# 10_-I2C-Switch.net
KiCad netlist of a schematic drawn in Altium Designer
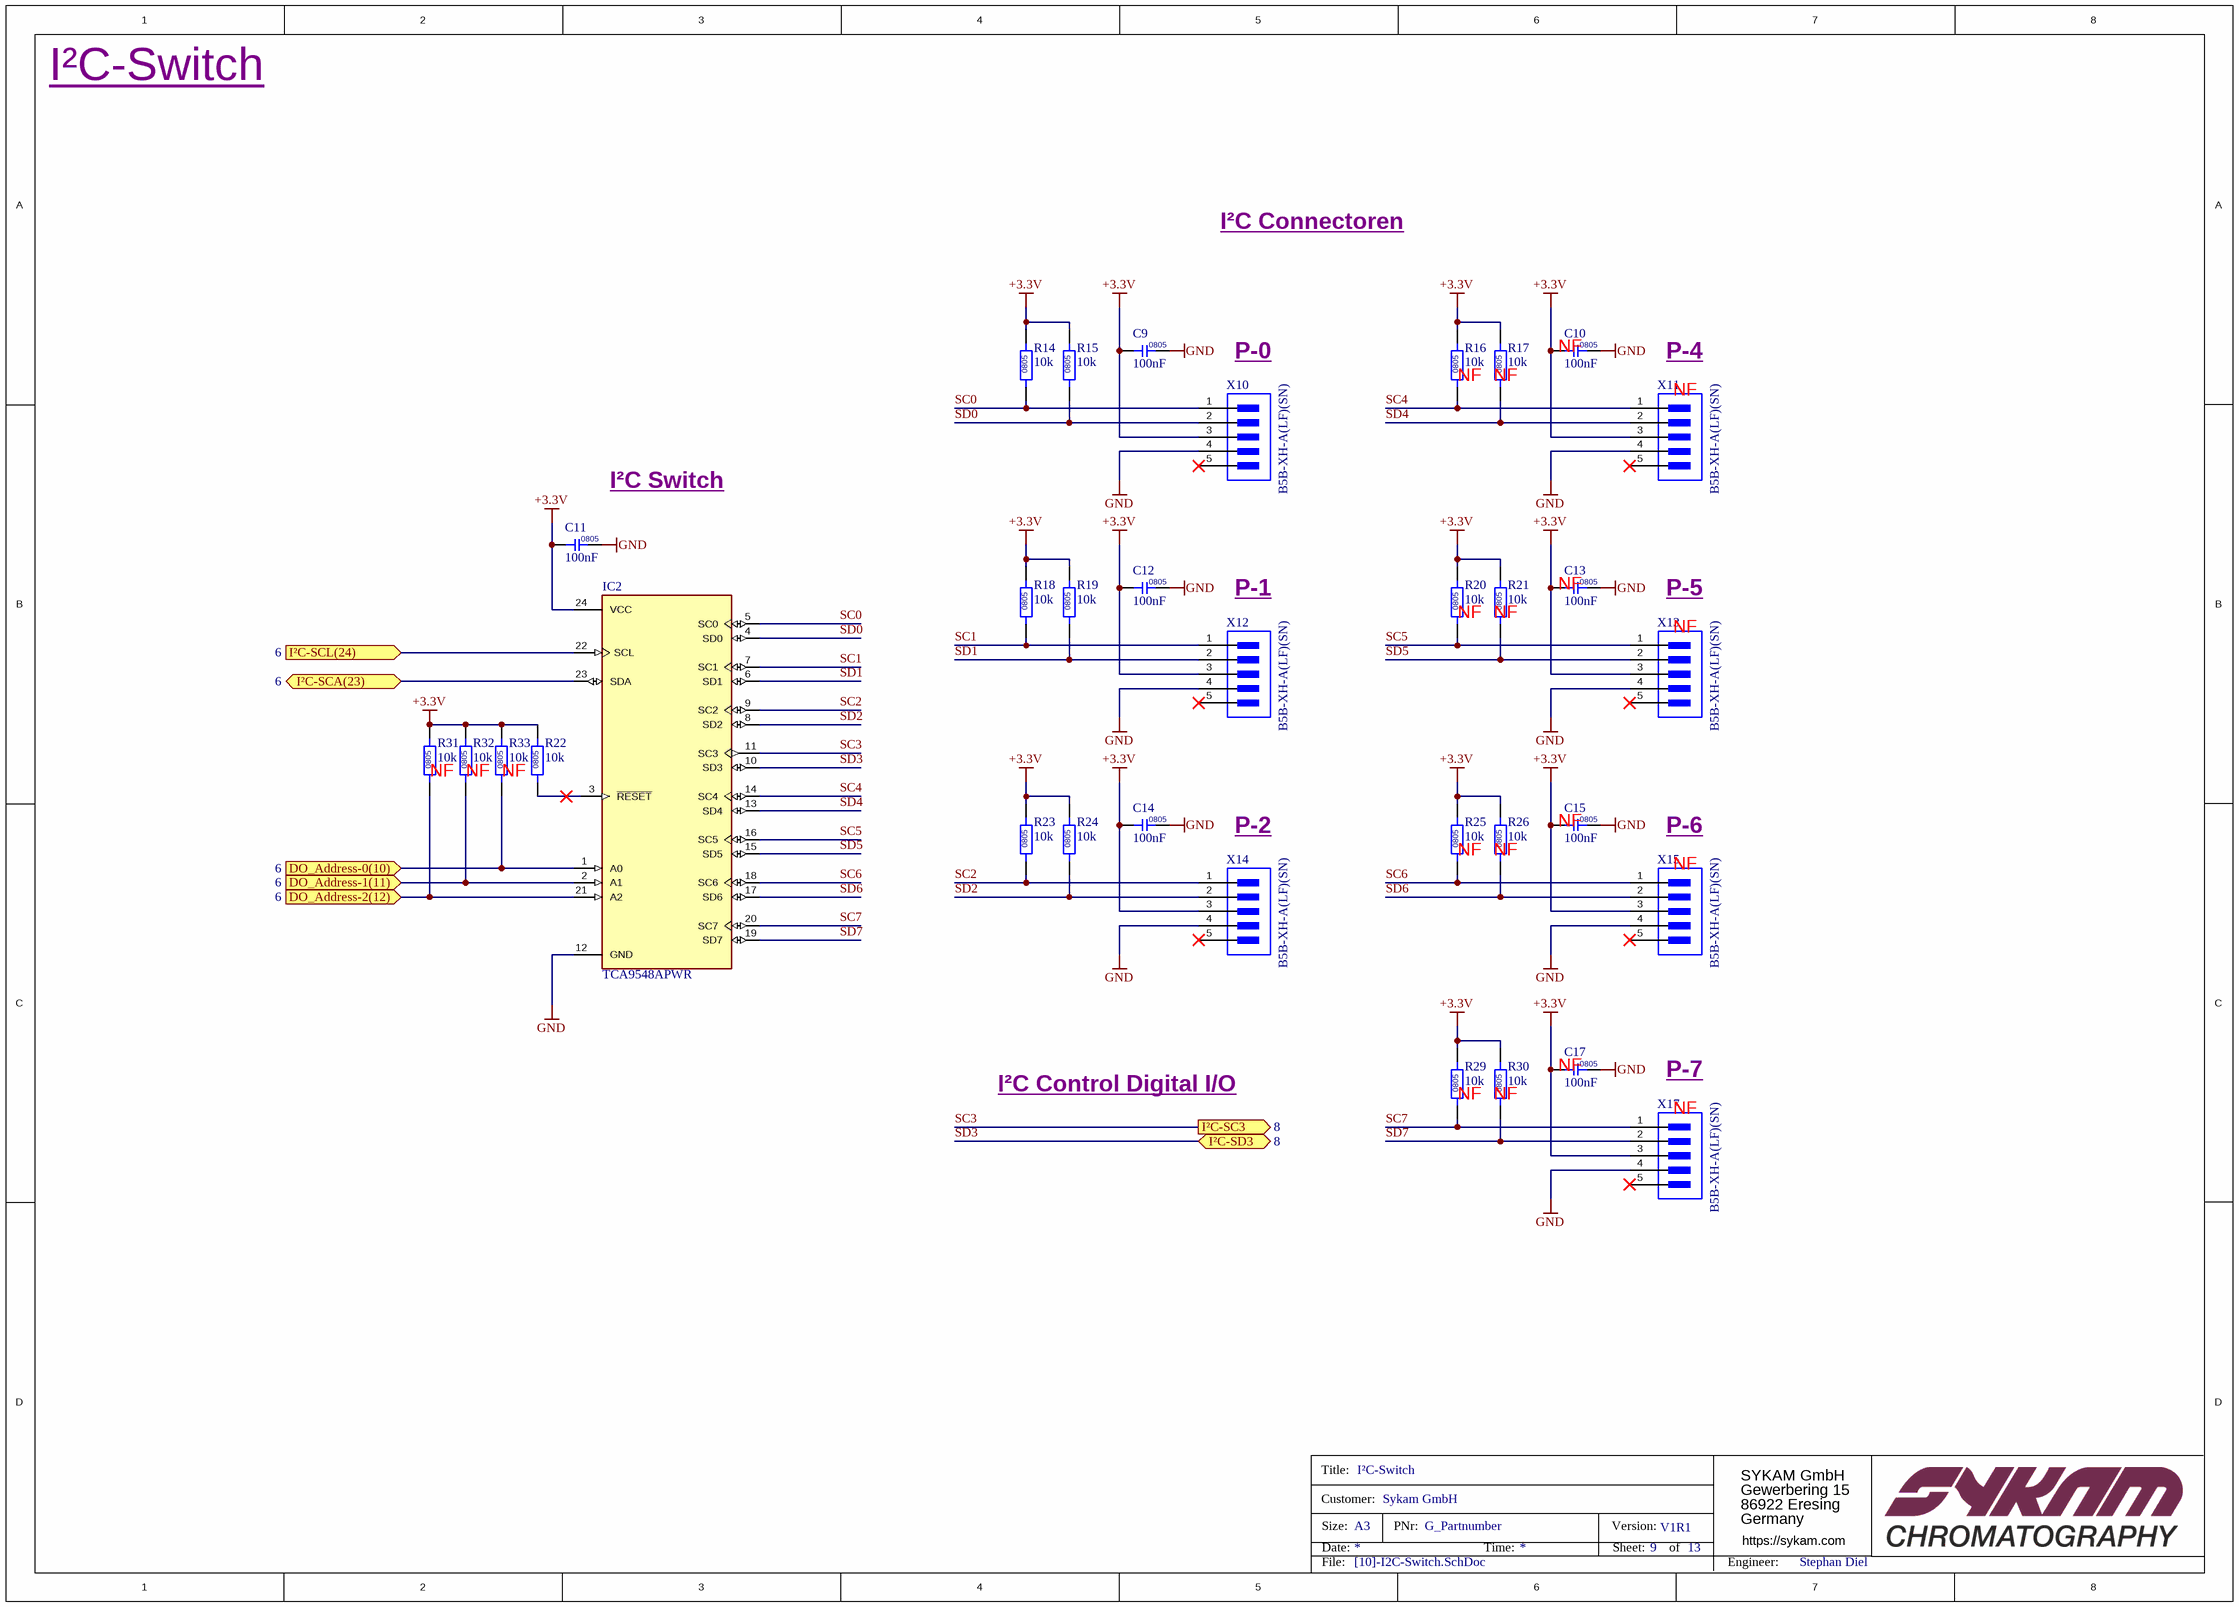
[diagram p0: [10]-I2C-Switch.SchDoc]

(export (version "E")
  (design (tool "Eeschema 10.0.6"))
  (components
    (comp (ref "C9")
      (value "100nF")
      (footprint "C0805")
      (description "CAP CER 0.1UF 50V X7R 0805")
      (fields
        (field (name "MANUFACTURER PART NUMBER") "CC0805KRX7R9BB104")
        (field (name "TOLERANCE") "10%")
        (field (name "PCBCHECKED") "initials after Checked")
        (field (name "SCHCHECKED") "Initials after checked")
      )
      (libsource (lib "ToradexMainBoard-V0I1") (part "C_100nF_CC0805KRX7R9BB104"))
    )
    (comp (ref "C10")
      (value "100nF")
      (footprint "C0805")
      (description "CAP CER 0.1UF 50V X7R 0805")
      (fields
        (field (name "MANUFACTURER PART NUMBER") "CC0805KRX7R9BB104")
        (field (name "TOLERANCE") "10%")
        (field (name "PCBCHECKED") "initials after Checked")
        (field (name "SCHCHECKED") "Initials after checked")
      )
      (libsource (lib "ToradexMainBoard-V0I1") (part "C_100nF_CC0805KRX7R9BB104"))
    )
    (comp (ref "C11")
      (value "100nF")
      (footprint "C0805")
      (description "CAP CER 0.1UF 50V X7R 0805")
      (fields
        (field (name "MANUFACTURER PART NUMBER") "CC0805KRX7R9BB104")
        (field (name "TOLERANCE") "10%")
        (field (name "PCBCHECKED") "initials after Checked")
        (field (name "SCHCHECKED") "Initials after checked")
      )
      (libsource (lib "ToradexMainBoard-V0I1") (part "C_100nF_CC0805KRX7R9BB104"))
    )
    (comp (ref "C12")
      (value "100nF")
      (footprint "C0805")
      (description "CAP CER 0.1UF 50V X7R 0805")
      (fields
        (field (name "MANUFACTURER PART NUMBER") "CC0805KRX7R9BB104")
        (field (name "TOLERANCE") "10%")
        (field (name "PCBCHECKED") "initials after Checked")
        (field (name "SCHCHECKED") "Initials after checked")
      )
      (libsource (lib "ToradexMainBoard-V0I1") (part "C_100nF_CC0805KRX7R9BB104"))
    )
    (comp (ref "C13")
      (value "100nF")
      (footprint "C0805")
      (description "CAP CER 0.1UF 50V X7R 0805")
      (fields
        (field (name "MANUFACTURER PART NUMBER") "CC0805KRX7R9BB104")
        (field (name "TOLERANCE") "10%")
        (field (name "PCBCHECKED") "initials after Checked")
        (field (name "SCHCHECKED") "Initials after checked")
      )
      (libsource (lib "ToradexMainBoard-V0I1") (part "C_100nF_CC0805KRX7R9BB104"))
    )
    (comp (ref "C14")
      (value "100nF")
      (footprint "C0805")
      (description "CAP CER 0.1UF 50V X7R 0805")
      (fields
        (field (name "MANUFACTURER PART NUMBER") "CC0805KRX7R9BB104")
        (field (name "TOLERANCE") "10%")
        (field (name "PCBCHECKED") "initials after Checked")
        (field (name "SCHCHECKED") "Initials after checked")
      )
      (libsource (lib "ToradexMainBoard-V0I1") (part "C_100nF_CC0805KRX7R9BB104"))
    )
    (comp (ref "C15")
      (value "100nF")
      (footprint "C0805")
      (description "CAP CER 0.1UF 50V X7R 0805")
      (fields
        (field (name "MANUFACTURER PART NUMBER") "CC0805KRX7R9BB104")
        (field (name "TOLERANCE") "10%")
        (field (name "PCBCHECKED") "initials after Checked")
        (field (name "SCHCHECKED") "Initials after checked")
      )
      (libsource (lib "ToradexMainBoard-V0I1") (part "C_100nF_CC0805KRX7R9BB104"))
    )
    (comp (ref "C17")
      (value "100nF")
      (footprint "C0805")
      (description "CAP CER 0.1UF 50V X7R 0805")
      (fields
        (field (name "MANUFACTURER PART NUMBER") "CC0805KRX7R9BB104")
        (field (name "TOLERANCE") "10%")
        (field (name "PCBCHECKED") "initials after Checked")
        (field (name "SCHCHECKED") "Initials after checked")
      )
      (libsource (lib "ToradexMainBoard-V0I1") (part "C_100nF_CC0805KRX7R9BB104"))
    )
    (comp (ref "IC2")
      (value "TCA9548APWR")
      (footprint "IC-TCA9548-TSSOP24")
      (description "IC I2C SW 8CH W/RESET 24TSSOP")
      (fields (field (name "MANUFACTURER") "Texas Instruments"))
      (libsource (lib "ToradexMainBoard-V0I1") (part "IC_TCA9548APWR"))
    )
    (comp (ref "R14")
      (value "10k")
      (footprint "R0805")
      (description "RES SMD 10K OHM 1% 1/8W 0805")
      (fields
        (field (name "MANUFACTURER PART NUMBER") "RC0805FR-0710KL")
        (field (name "TOLERANCE") "1%")
        (field (name "PCBCHECKED") "initials after Checked")
        (field (name "SCHCHECKED") "Initials after checked")
      )
      (libsource (lib "ToradexMainBoard-V0I1") (part "R_10k_RC0805FR-0710KL"))
    )
    (comp (ref "R15")
      (value "10k")
      (footprint "R0805")
      (description "RES SMD 10K OHM 1% 1/8W 0805")
      (fields
        (field (name "MANUFACTURER PART NUMBER") "RC0805FR-0710KL")
        (field (name "TOLERANCE") "1%")
        (field (name "PCBCHECKED") "initials after Checked")
        (field (name "SCHCHECKED") "Initials after checked")
      )
      (libsource (lib "ToradexMainBoard-V0I1") (part "R_10k_RC0805FR-0710KL"))
    )
    (comp (ref "R16")
      (value "10k")
      (footprint "R0805")
      (description "RES SMD 10K OHM 1% 1/8W 0805")
      (fields
        (field (name "MANUFACTURER PART NUMBER") "RC0805FR-0710KL")
        (field (name "TOLERANCE") "1%")
        (field (name "PCBCHECKED") "initials after Checked")
        (field (name "SCHCHECKED") "Initials after checked")
      )
      (libsource (lib "ToradexMainBoard-V0I1") (part "R_10k_RC0805FR-0710KL"))
    )
    (comp (ref "R17")
      (value "10k")
      (footprint "R0805")
      (description "RES SMD 10K OHM 1% 1/8W 0805")
      (fields
        (field (name "MANUFACTURER PART NUMBER") "RC0805FR-0710KL")
        (field (name "TOLERANCE") "1%")
        (field (name "PCBCHECKED") "initials after Checked")
        (field (name "SCHCHECKED") "Initials after checked")
      )
      (libsource (lib "ToradexMainBoard-V0I1") (part "R_10k_RC0805FR-0710KL"))
    )
    (comp (ref "R18")
      (value "10k")
      (footprint "R0805")
      (description "RES SMD 10K OHM 1% 1/8W 0805")
      (fields
        (field (name "MANUFACTURER PART NUMBER") "RC0805FR-0710KL")
        (field (name "TOLERANCE") "1%")
        (field (name "PCBCHECKED") "initials after Checked")
        (field (name "SCHCHECKED") "Initials after checked")
      )
      (libsource (lib "ToradexMainBoard-V0I1") (part "R_10k_RC0805FR-0710KL"))
    )
    (comp (ref "R19")
      (value "10k")
      (footprint "R0805")
      (description "RES SMD 10K OHM 1% 1/8W 0805")
      (fields
        (field (name "MANUFACTURER PART NUMBER") "RC0805FR-0710KL")
        (field (name "TOLERANCE") "1%")
        (field (name "PCBCHECKED") "initials after Checked")
        (field (name "SCHCHECKED") "Initials after checked")
      )
      (libsource (lib "ToradexMainBoard-V0I1") (part "R_10k_RC0805FR-0710KL"))
    )
    (comp (ref "R20")
      (value "10k")
      (footprint "R0805")
      (description "RES SMD 10K OHM 1% 1/8W 0805")
      (fields
        (field (name "MANUFACTURER PART NUMBER") "RC0805FR-0710KL")
        (field (name "TOLERANCE") "1%")
        (field (name "PCBCHECKED") "initials after Checked")
        (field (name "SCHCHECKED") "Initials after checked")
      )
      (libsource (lib "ToradexMainBoard-V0I1") (part "R_10k_RC0805FR-0710KL"))
    )
    (comp (ref "R21")
      (value "10k")
      (footprint "R0805")
      (description "RES SMD 10K OHM 1% 1/8W 0805")
      (fields
        (field (name "MANUFACTURER PART NUMBER") "RC0805FR-0710KL")
        (field (name "TOLERANCE") "1%")
        (field (name "PCBCHECKED") "initials after Checked")
        (field (name "SCHCHECKED") "Initials after checked")
      )
      (libsource (lib "ToradexMainBoard-V0I1") (part "R_10k_RC0805FR-0710KL"))
    )
    (comp (ref "R22")
      (value "10k")
      (footprint "R0805")
      (description "RES SMD 10K OHM 1% 1/8W 0805")
      (fields
        (field (name "MANUFACTURER PART NUMBER") "RC0805FR-0710KL")
        (field (name "TOLERANCE") "1%")
        (field (name "PCBCHECKED") "initials after Checked")
        (field (name "SCHCHECKED") "Initials after checked")
      )
      (libsource (lib "ToradexMainBoard-V0I1") (part "R_10k_RC0805FR-0710KL"))
    )
    (comp (ref "R23")
      (value "10k")
      (footprint "R0805")
      (description "RES SMD 10K OHM 1% 1/8W 0805")
      (fields
        (field (name "MANUFACTURER PART NUMBER") "RC0805FR-0710KL")
        (field (name "TOLERANCE") "1%")
        (field (name "PCBCHECKED") "initials after Checked")
        (field (name "SCHCHECKED") "Initials after checked")
      )
      (libsource (lib "ToradexMainBoard-V0I1") (part "R_10k_RC0805FR-0710KL"))
    )
    (comp (ref "R24")
      (value "10k")
      (footprint "R0805")
      (description "RES SMD 10K OHM 1% 1/8W 0805")
      (fields
        (field (name "MANUFACTURER PART NUMBER") "RC0805FR-0710KL")
        (field (name "TOLERANCE") "1%")
        (field (name "PCBCHECKED") "initials after Checked")
        (field (name "SCHCHECKED") "Initials after checked")
      )
      (libsource (lib "ToradexMainBoard-V0I1") (part "R_10k_RC0805FR-0710KL"))
    )
    (comp (ref "R25")
      (value "10k")
      (footprint "R0805")
      (description "RES SMD 10K OHM 1% 1/8W 0805")
      (fields
        (field (name "MANUFACTURER PART NUMBER") "RC0805FR-0710KL")
        (field (name "TOLERANCE") "1%")
        (field (name "PCBCHECKED") "initials after Checked")
        (field (name "SCHCHECKED") "Initials after checked")
      )
      (libsource (lib "ToradexMainBoard-V0I1") (part "R_10k_RC0805FR-0710KL"))
    )
    (comp (ref "R26")
      (value "10k")
      (footprint "R0805")
      (description "RES SMD 10K OHM 1% 1/8W 0805")
      (fields
        (field (name "MANUFACTURER PART NUMBER") "RC0805FR-0710KL")
        (field (name "TOLERANCE") "1%")
        (field (name "PCBCHECKED") "initials after Checked")
        (field (name "SCHCHECKED") "Initials after checked")
      )
      (libsource (lib "ToradexMainBoard-V0I1") (part "R_10k_RC0805FR-0710KL"))
    )
    (comp (ref "R29")
      (value "10k")
      (footprint "R0805")
      (description "RES SMD 10K OHM 1% 1/8W 0805")
      (fields
        (field (name "MANUFACTURER PART NUMBER") "RC0805FR-0710KL")
        (field (name "TOLERANCE") "1%")
        (field (name "PCBCHECKED") "initials after Checked")
        (field (name "SCHCHECKED") "Initials after checked")
      )
      (libsource (lib "ToradexMainBoard-V0I1") (part "R_10k_RC0805FR-0710KL"))
    )
    (comp (ref "R30")
      (value "10k")
      (footprint "R0805")
      (description "RES SMD 10K OHM 1% 1/8W 0805")
      (fields
        (field (name "MANUFACTURER PART NUMBER") "RC0805FR-0710KL")
        (field (name "TOLERANCE") "1%")
        (field (name "PCBCHECKED") "initials after Checked")
        (field (name "SCHCHECKED") "Initials after checked")
      )
      (libsource (lib "ToradexMainBoard-V0I1") (part "R_10k_RC0805FR-0710KL"))
    )
    (comp (ref "R31")
      (value "10k")
      (footprint "R0805")
      (description "RES SMD 10K OHM 1% 1/8W 0805")
      (fields
        (field (name "MANUFACTURER PART NUMBER") "RC0805FR-0710KL")
        (field (name "TOLERANCE") "1%")
        (field (name "PCBCHECKED") "initials after Checked")
        (field (name "SCHCHECKED") "Initials after checked")
      )
      (libsource (lib "ToradexMainBoard-V0I1") (part "R_10k_RC0805FR-0710KL"))
    )
    (comp (ref "R32")
      (value "10k")
      (footprint "R0805")
      (description "RES SMD 10K OHM 1% 1/8W 0805")
      (fields
        (field (name "MANUFACTURER PART NUMBER") "RC0805FR-0710KL")
        (field (name "TOLERANCE") "1%")
        (field (name "PCBCHECKED") "initials after Checked")
        (field (name "SCHCHECKED") "Initials after checked")
      )
      (libsource (lib "ToradexMainBoard-V0I1") (part "R_10k_RC0805FR-0710KL"))
    )
    (comp (ref "R33")
      (value "10k")
      (footprint "R0805")
      (description "RES SMD 10K OHM 1% 1/8W 0805")
      (fields
        (field (name "MANUFACTURER PART NUMBER") "RC0805FR-0710KL")
        (field (name "TOLERANCE") "1%")
        (field (name "PCBCHECKED") "initials after Checked")
        (field (name "SCHCHECKED") "Initials after checked")
      )
      (libsource (lib "ToradexMainBoard-V0I1") (part "R_10k_RC0805FR-0710KL"))
    )
    (comp (ref "X10")
      (value "B5B-XH-A(LF)(SN)")
      (footprint "CON_ B5B-XH-A (LF)(SN)")
      (description "Conn Shrouded Header HDR 5 POS 2.5mm Solder ST Thru-Hole Box")
      (fields (field (name "MANUFACTURER") "JST"))
      (libsource (lib "ToradexMainBoard-V0I1") (part "CON_5p_B5B-XH-A(LF)(SN)"))
    )
    (comp (ref "X11")
      (value "B5B-XH-A(LF)(SN)")
      (footprint "CON_ B5B-XH-A (LF)(SN)")
      (description "Conn Shrouded Header HDR 5 POS 2.5mm Solder ST Thru-Hole Box")
      (fields (field (name "MANUFACTURER") "JST"))
      (libsource (lib "ToradexMainBoard-V0I1") (part "CON_5p_B5B-XH-A(LF)(SN)"))
    )
    (comp (ref "X12")
      (value "B5B-XH-A(LF)(SN)")
      (footprint "CON_ B5B-XH-A (LF)(SN)")
      (description "Conn Shrouded Header HDR 5 POS 2.5mm Solder ST Thru-Hole Box")
      (fields (field (name "MANUFACTURER") "JST"))
      (libsource (lib "ToradexMainBoard-V0I1") (part "CON_5p_B5B-XH-A(LF)(SN)"))
    )
    (comp (ref "X13")
      (value "B5B-XH-A(LF)(SN)")
      (footprint "CON_ B5B-XH-A (LF)(SN)")
      (description "Conn Shrouded Header HDR 5 POS 2.5mm Solder ST Thru-Hole Box")
      (fields (field (name "MANUFACTURER") "JST"))
      (libsource (lib "ToradexMainBoard-V0I1") (part "CON_5p_B5B-XH-A(LF)(SN)"))
    )
    (comp (ref "X14")
      (value "B5B-XH-A(LF)(SN)")
      (footprint "CON_ B5B-XH-A (LF)(SN)")
      (description "Conn Shrouded Header HDR 5 POS 2.5mm Solder ST Thru-Hole Box")
      (fields (field (name "MANUFACTURER") "JST"))
      (libsource (lib "ToradexMainBoard-V0I1") (part "CON_5p_B5B-XH-A(LF)(SN)"))
    )
    (comp (ref "X15")
      (value "B5B-XH-A(LF)(SN)")
      (footprint "CON_ B5B-XH-A (LF)(SN)")
      (description "Conn Shrouded Header HDR 5 POS 2.5mm Solder ST Thru-Hole Box")
      (fields (field (name "MANUFACTURER") "JST"))
      (libsource (lib "ToradexMainBoard-V0I1") (part "CON_5p_B5B-XH-A(LF)(SN)"))
    )
    (comp (ref "X17")
      (value "B5B-XH-A(LF)(SN)")
      (footprint "CON_ B5B-XH-A (LF)(SN)")
      (description "Conn Shrouded Header HDR 5 POS 2.5mm Solder ST Thru-Hole Box")
      (fields (field (name "MANUFACTURER") "JST"))
      (libsource (lib "ToradexMainBoard-V0I1") (part "CON_5p_B5B-XH-A(LF)(SN)"))
    )
  )
  (nets
    (net (code "1") (name "+3.3V") (class "Default")
      (node (ref "C10") (pin "1") (pinfunction "1_1") (pintype "passive"))
      (node (ref "C11") (pin "1") (pinfunction "1_1") (pintype "passive"))
      (node (ref "C12") (pin "1") (pinfunction "1_1") (pintype "passive"))
      (node (ref "C13") (pin "1") (pinfunction "1_1") (pintype "passive"))
      (node (ref "C14") (pin "1") (pinfunction "1_1") (pintype "passive"))
      (node (ref "C15") (pin "1") (pinfunction "1_1") (pintype "passive"))
      (node (ref "C17") (pin "1") (pinfunction "1_1") (pintype "passive"))
      (node (ref "C9") (pin "1") (pinfunction "1_1") (pintype "passive"))
      (node (ref "IC2") (pin "24") (pinfunction "VCC_24") (pintype "power_in"))
      (node (ref "R14") (pin "2") (pinfunction "2_2") (pintype "passive"))
      (node (ref "R15") (pin "2") (pinfunction "2_2") (pintype "passive"))
      (node (ref "R16") (pin "2") (pinfunction "2_2") (pintype "passive"))
      (node (ref "R17") (pin "2") (pinfunction "2_2") (pintype "passive"))
      (node (ref "R18") (pin "2") (pinfunction "2_2") (pintype "passive"))
      (node (ref "R19") (pin "2") (pinfunction "2_2") (pintype "passive"))
      (node (ref "R20") (pin "2") (pinfunction "2_2") (pintype "passive"))
      (node (ref "R21") (pin "2") (pinfunction "2_2") (pintype "passive"))
      (node (ref "R22") (pin "2") (pinfunction "2_2") (pintype "passive"))
      (node (ref "R23") (pin "2") (pinfunction "2_2") (pintype "passive"))
      (node (ref "R24") (pin "2") (pinfunction "2_2") (pintype "passive"))
      (node (ref "R25") (pin "2") (pinfunction "2_2") (pintype "passive"))
      (node (ref "R26") (pin "2") (pinfunction "2_2") (pintype "passive"))
      (node (ref "R29") (pin "2") (pinfunction "2_2") (pintype "passive"))
      (node (ref "R30") (pin "2") (pinfunction "2_2") (pintype "passive"))
      (node (ref "R31") (pin "2") (pinfunction "2_2") (pintype "passive"))
      (node (ref "R32") (pin "2") (pinfunction "2_2") (pintype "passive"))
      (node (ref "R33") (pin "2") (pinfunction "2_2") (pintype "passive"))
      (node (ref "X10") (pin "3") (pintype "passive"))
      (node (ref "X11") (pin "3") (pintype "passive"))
      (node (ref "X12") (pin "3") (pintype "passive"))
      (node (ref "X13") (pin "3") (pintype "passive"))
      (node (ref "X14") (pin "3") (pintype "passive"))
      (node (ref "X15") (pin "3") (pintype "passive"))
      (node (ref "X17") (pin "3") (pintype "passive"))
    )
    (net (code "2") (name "/DO_Address-0(10)") (class "Default")
      (node (ref "IC2") (pin "1") (pinfunction "A0_1") (pintype "input"))
      (node (ref "R33") (pin "1") (pinfunction "1_1") (pintype "passive"))
    )
    (net (code "3") (name "/DO_Address-1(11)") (class "Default")
      (node (ref "IC2") (pin "2") (pinfunction "A1_2") (pintype "input"))
      (node (ref "R32") (pin "1") (pinfunction "1_1") (pintype "passive"))
    )
    (net (code "4") (name "/DO_Address-2(12)") (class "Default")
      (node (ref "IC2") (pin "21") (pinfunction "A2_21") (pintype "input"))
      (node (ref "R31") (pin "1") (pinfunction "1_1") (pintype "passive"))
    )
    (net (code "5") (name "/I²C-SCA(23)") (class "Default")
      (node (ref "IC2") (pin "23") (pinfunction "SDA_23") (pintype "bidirectional"))
    )
    (net (code "6") (name "/I²C-SCL(24)") (class "Default")
      (node (ref "IC2") (pin "22") (pinfunction "SCL_22") (pintype "input"))
    )
    (net (code "7") (name "/SC0") (class "Default")
      (node (ref "IC2") (pin "5") (pinfunction "SC0_5") (pintype "bidirectional"))
      (node (ref "R14") (pin "1") (pinfunction "1_1") (pintype "passive"))
      (node (ref "X10") (pin "1") (pintype "passive"))
    )
    (net (code "8") (name "/SC1") (class "Default")
      (node (ref "IC2") (pin "7") (pinfunction "SC1_7") (pintype "bidirectional"))
      (node (ref "R18") (pin "1") (pinfunction "1_1") (pintype "passive"))
      (node (ref "X12") (pin "1") (pintype "passive"))
    )
    (net (code "9") (name "/SC2") (class "Default")
      (node (ref "IC2") (pin "9") (pinfunction "SC2_9") (pintype "bidirectional"))
      (node (ref "R23") (pin "1") (pinfunction "1_1") (pintype "passive"))
      (node (ref "X14") (pin "1") (pintype "passive"))
    )
    (net (code "10") (name "/SC3") (class "Default")
      (node (ref "IC2") (pin "11") (pinfunction "SC3_11") (pintype "output"))
    )
    (net (code "11") (name "/SC4") (class "Default")
      (node (ref "IC2") (pin "14") (pinfunction "SC4_14") (pintype "bidirectional"))
      (node (ref "R16") (pin "1") (pinfunction "1_1") (pintype "passive"))
      (node (ref "X11") (pin "1") (pintype "passive"))
    )
    (net (code "12") (name "/SC5") (class "Default")
      (node (ref "IC2") (pin "16") (pinfunction "SC5_16") (pintype "bidirectional"))
      (node (ref "R20") (pin "1") (pinfunction "1_1") (pintype "passive"))
      (node (ref "X13") (pin "1") (pintype "passive"))
    )
    (net (code "13") (name "/SC6") (class "Default")
      (node (ref "IC2") (pin "18") (pinfunction "SC6_18") (pintype "bidirectional"))
      (node (ref "R25") (pin "1") (pinfunction "1_1") (pintype "passive"))
      (node (ref "X15") (pin "1") (pintype "passive"))
    )
    (net (code "14") (name "/SC7") (class "Default")
      (node (ref "IC2") (pin "20") (pinfunction "SC7_20") (pintype "bidirectional"))
      (node (ref "R29") (pin "1") (pinfunction "1_1") (pintype "passive"))
      (node (ref "X17") (pin "1") (pintype "passive"))
    )
    (net (code "15") (name "/SD0") (class "Default")
      (node (ref "IC2") (pin "4") (pinfunction "SD0_4") (pintype "bidirectional"))
      (node (ref "R15") (pin "1") (pinfunction "1_1") (pintype "passive"))
      (node (ref "X10") (pin "2") (pintype "passive"))
    )
    (net (code "16") (name "/SD1") (class "Default")
      (node (ref "IC2") (pin "6") (pinfunction "SD1_6") (pintype "bidirectional"))
      (node (ref "R19") (pin "1") (pinfunction "1_1") (pintype "passive"))
      (node (ref "X12") (pin "2") (pintype "passive"))
    )
    (net (code "17") (name "/SD2") (class "Default")
      (node (ref "IC2") (pin "8") (pinfunction "SD2_8") (pintype "bidirectional"))
      (node (ref "R24") (pin "1") (pinfunction "1_1") (pintype "passive"))
      (node (ref "X14") (pin "2") (pintype "passive"))
    )
    (net (code "18") (name "/SD3") (class "Default")
      (node (ref "IC2") (pin "10") (pinfunction "SD3_10") (pintype "bidirectional"))
    )
    (net (code "19") (name "/SD4") (class "Default")
      (node (ref "IC2") (pin "13") (pinfunction "SD4_13") (pintype "bidirectional"))
      (node (ref "R17") (pin "1") (pinfunction "1_1") (pintype "passive"))
      (node (ref "X11") (pin "2") (pintype "passive"))
    )
    (net (code "20") (name "/SD5") (class "Default")
      (node (ref "IC2") (pin "15") (pinfunction "SD5_15") (pintype "bidirectional"))
      (node (ref "R21") (pin "1") (pinfunction "1_1") (pintype "passive"))
      (node (ref "X13") (pin "2") (pintype "passive"))
    )
    (net (code "21") (name "/SD6") (class "Default")
      (node (ref "IC2") (pin "17") (pinfunction "SD6_17") (pintype "bidirectional"))
      (node (ref "R26") (pin "1") (pinfunction "1_1") (pintype "passive"))
      (node (ref "X15") (pin "2") (pintype "passive"))
    )
    (net (code "22") (name "/SD7") (class "Default")
      (node (ref "IC2") (pin "19") (pinfunction "SD7_19") (pintype "bidirectional"))
      (node (ref "R30") (pin "1") (pinfunction "1_1") (pintype "passive"))
      (node (ref "X17") (pin "2") (pintype "passive"))
    )
    (net (code "23") (name "GND") (class "Default")
      (node (ref "C10") (pin "2") (pinfunction "2_2") (pintype "passive"))
      (node (ref "C11") (pin "2") (pinfunction "2_2") (pintype "passive"))
      (node (ref "C12") (pin "2") (pinfunction "2_2") (pintype "passive"))
      (node (ref "C13") (pin "2") (pinfunction "2_2") (pintype "passive"))
      (node (ref "C14") (pin "2") (pinfunction "2_2") (pintype "passive"))
      (node (ref "C15") (pin "2") (pinfunction "2_2") (pintype "passive"))
      (node (ref "C17") (pin "2") (pinfunction "2_2") (pintype "passive"))
      (node (ref "C9") (pin "2") (pinfunction "2_2") (pintype "passive"))
      (node (ref "IC2") (pin "12") (pinfunction "GND_12") (pintype "power_in"))
      (node (ref "X10") (pin "4") (pintype "passive"))
      (node (ref "X11") (pin "4") (pintype "passive"))
      (node (ref "X12") (pin "4") (pintype "passive"))
      (node (ref "X13") (pin "4") (pintype "passive"))
      (node (ref "X14") (pin "4") (pintype "passive"))
      (node (ref "X15") (pin "4") (pintype "passive"))
      (node (ref "X17") (pin "4") (pintype "passive"))
    )
    (net (code "24") (name "Net-(IC2-~{RESET})") (class "Default")
      (node (ref "IC2") (pin "3") (pinfunction "~{RESET}_3") (pintype "input"))
      (node (ref "R22") (pin "1") (pinfunction "1_1") (pintype "passive"))
    )
    (net (code "25") (name "unconnected-(X10-Pad5)") (class "Default")
      (node (ref "X10") (pin "5") (pintype "passive+no_connect"))
    )
    (net (code "26") (name "unconnected-(X11-Pad5)") (class "Default")
      (node (ref "X11") (pin "5") (pintype "passive+no_connect"))
    )
    (net (code "27") (name "unconnected-(X12-Pad5)") (class "Default")
      (node (ref "X12") (pin "5") (pintype "passive+no_connect"))
    )
    (net (code "28") (name "unconnected-(X13-Pad5)") (class "Default")
      (node (ref "X13") (pin "5") (pintype "passive+no_connect"))
    )
    (net (code "29") (name "unconnected-(X14-Pad5)") (class "Default")
      (node (ref "X14") (pin "5") (pintype "passive+no_connect"))
    )
    (net (code "30") (name "unconnected-(X15-Pad5)") (class "Default")
      (node (ref "X15") (pin "5") (pintype "passive+no_connect"))
    )
    (net (code "31") (name "unconnected-(X17-Pad5)") (class "Default")
      (node (ref "X17") (pin "5") (pintype "passive+no_connect"))
    )
  )
)
